# Devices.net
KiCad netlist of a schematic drawn in Altium Designer
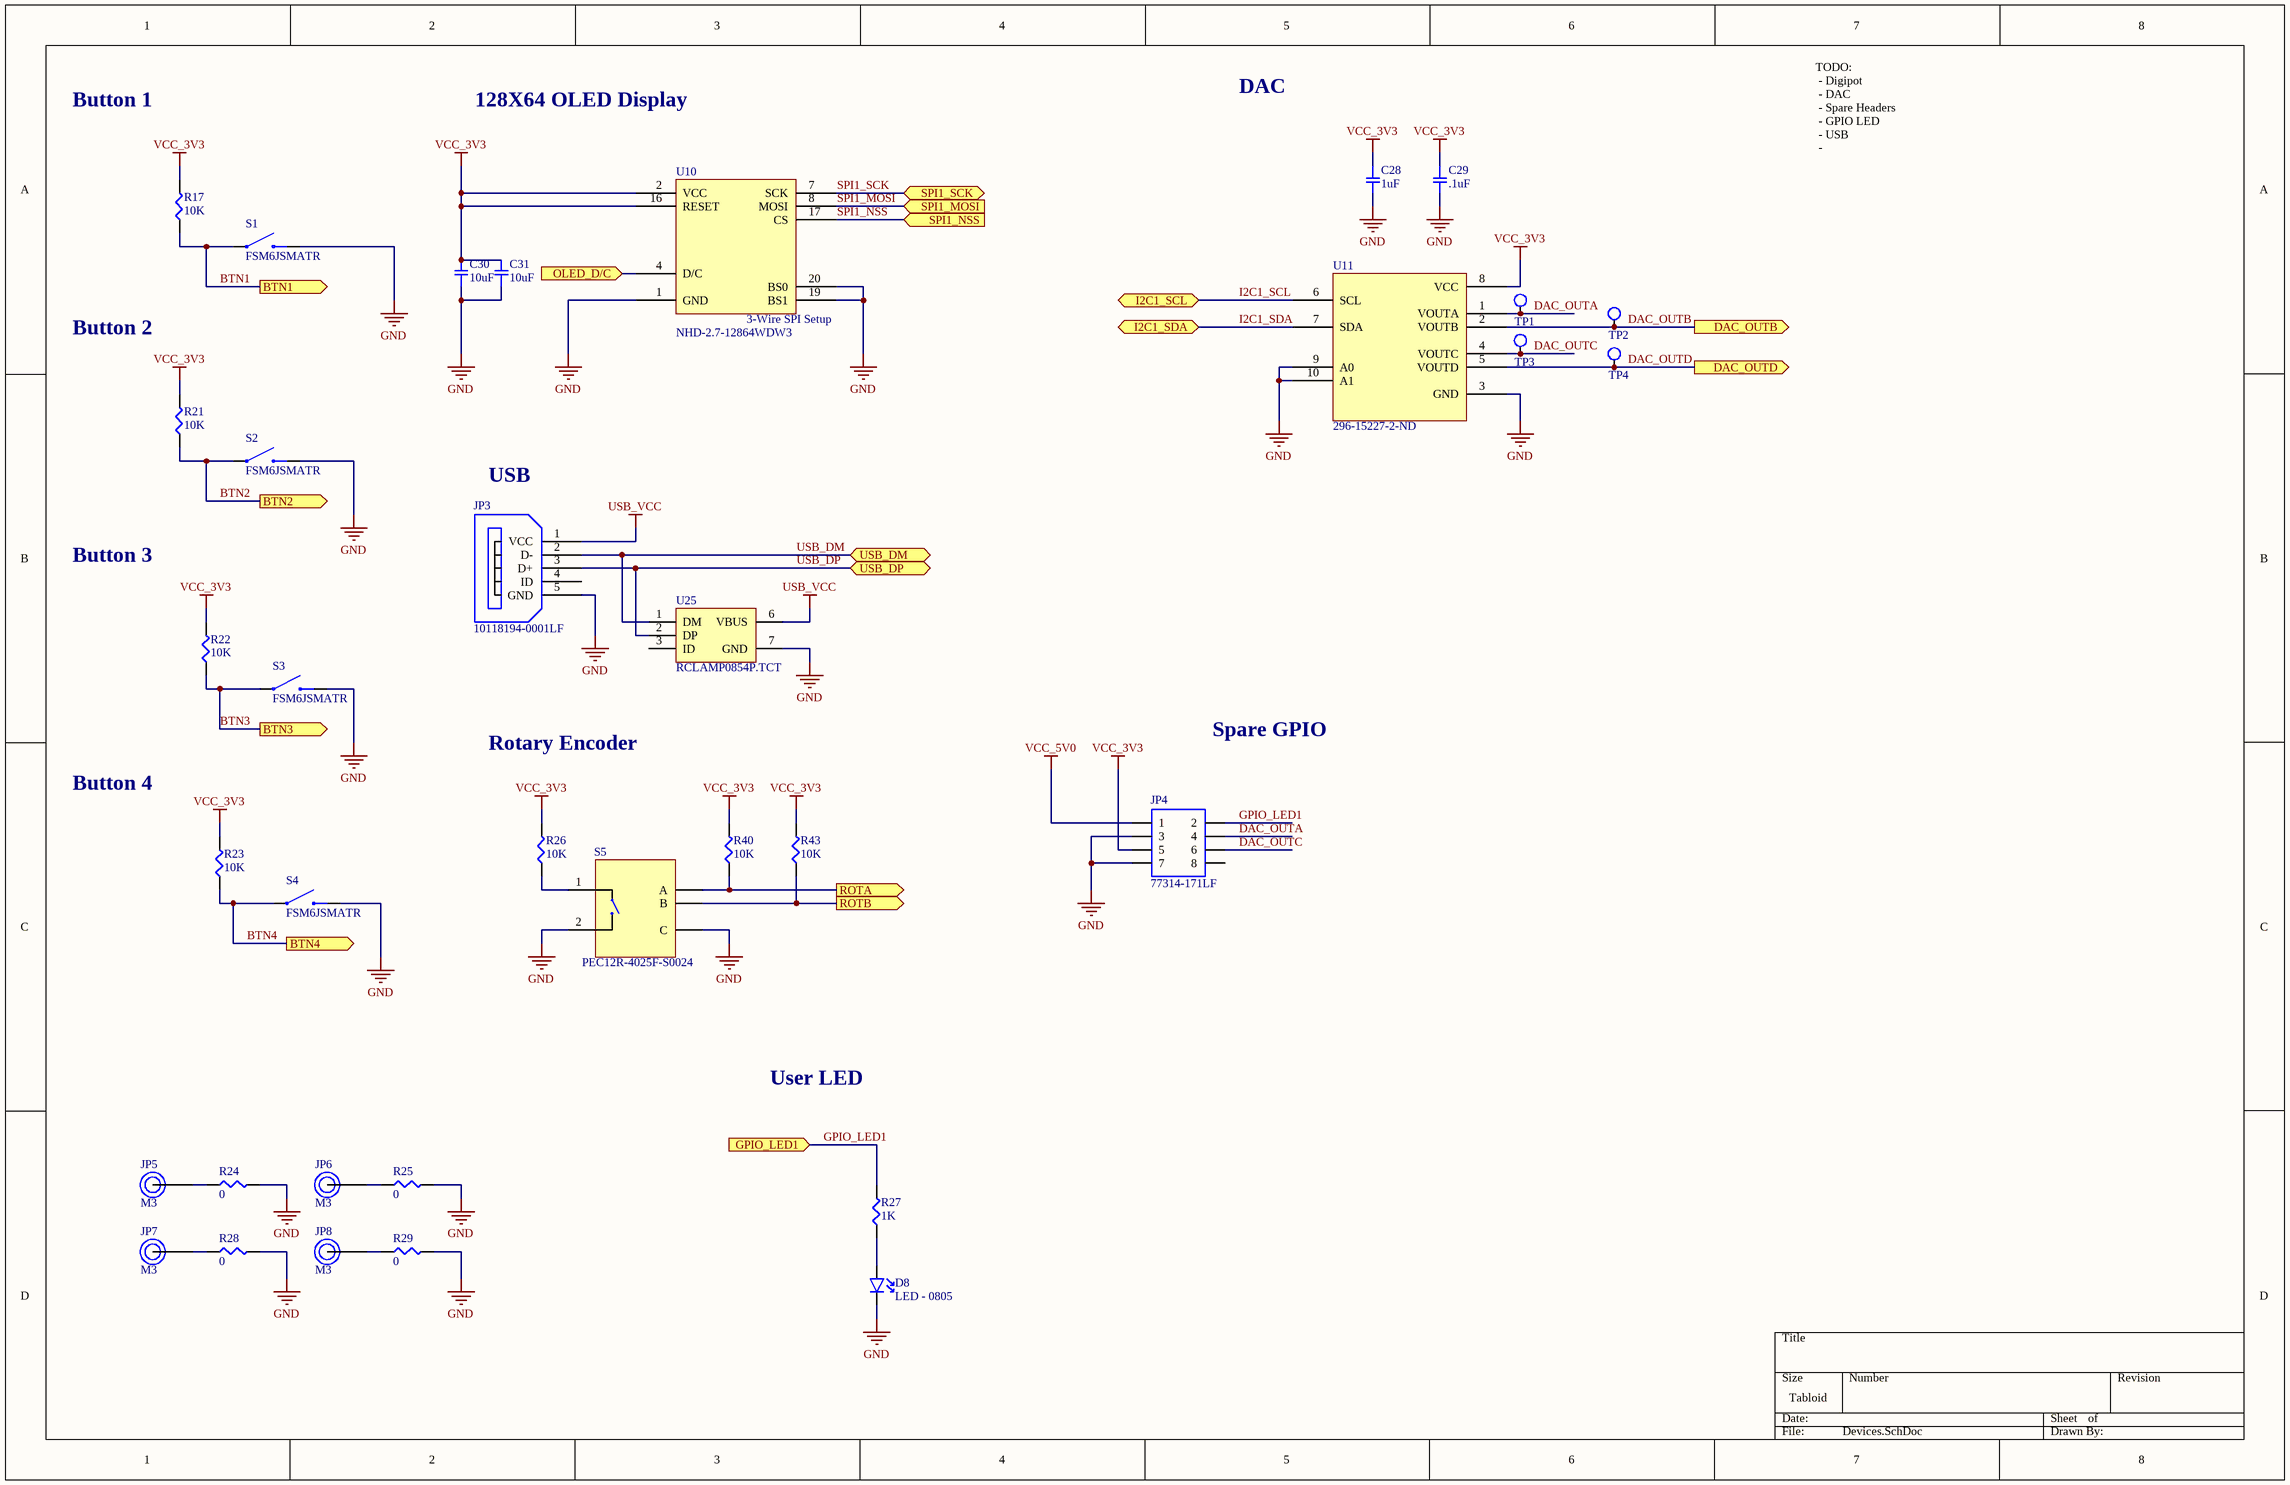
[diagram p0: Devices.SchDoc]

(export (version "E")
  (design (tool "Eeschema 10.0.6"))
  (components
    (comp (ref "C28")
      (value "1uF")
      (footprint "SMD-0603C")
      (description "CAP CER 0.022UF 50V X7R 0603")
      (fields
        (field (name "DIGI-KEY PART NUMBER") "490-5851-1-ND")
        (field (name "PART NUMBER") "GCJ188R71H223KA01D")
      )
      (libsource (lib "capacitor_murata_0603") (part "GCJ188R71H223KA01D"))
    )
    (comp (ref "C29")
      (value ".1uF")
      (footprint "SMD-0603C")
      (description "CAP CER 0.022UF 50V X7R 0603")
      (fields
        (field (name "DIGI-KEY PART NUMBER") "490-5851-1-ND")
        (field (name "PART NUMBER") "GCJ188R71H223KA01D")
      )
      (libsource (lib "capacitor_murata_0603") (part "GCJ188R71H223KA01D"))
    )
    (comp (ref "C30")
      (value "10uF")
      (footprint "SMD-0805C")
      (description "CAP CER 0.1UF 16V X7R 0805")
      (fields
        (field (name "DIGI-KEY PART NUMBER") "490-4414-1-ND")
        (field (name "PART NUMBER") "LLA219R71C104MA01L")
      )
      (libsource (lib "capacitor_murata_0805") (part "LLA219R71C104MA01L"))
    )
    (comp (ref "C31")
      (value "10uF")
      (footprint "SMD-0805C")
      (description "CAP CER 0.1UF 16V X7R 0805")
      (fields
        (field (name "DIGI-KEY PART NUMBER") "490-4414-1-ND")
        (field (name "PART NUMBER") "LLA219R71C104MA01L")
      )
      (libsource (lib "capacitor_murata_0805") (part "LLA219R71C104MA01L"))
    )
    (comp (ref "D8")
      (value "LED - 0805")
      (footprint "0805 SMD")
      (libsource (lib "Personal_Library") (part "LED - 0805"))
    )
    (comp (ref "JP3")
      (value "10118194-0001LF")
      (footprint "014-439")
      (description "CONN RCPT USB2.0 MICRO B SMD R/A")
      (libsource (lib "Personal_Library") (part "CONN USB"))
    )
    (comp (ref "JP4")
      (value "77314-171LF")
      (footprint "2x4 Pin Header")
      (description "CONN HEADER VERT 8POS 2.54MM")
      (libsource (lib "Personal_Library") (part "CONN HEADER VERT 2x4"))
    )
    (comp (ref "JP5")
      (value "M3")
      (footprint "M3-Hole")
      (description "M3 MOUNT HOLE SIZE")
      (libsource (lib "Personal_Library") (part "HOLE MOUNT M3"))
    )
    (comp (ref "JP6")
      (value "M3")
      (footprint "M3-Hole")
      (description "M3 MOUNT HOLE SIZE")
      (libsource (lib "Personal_Library") (part "HOLE MOUNT M3"))
    )
    (comp (ref "JP7")
      (value "M3")
      (footprint "M3-Hole")
      (description "M3 MOUNT HOLE SIZE")
      (libsource (lib "Personal_Library") (part "HOLE MOUNT M3"))
    )
    (comp (ref "JP8")
      (value "M3")
      (footprint "M3-Hole")
      (description "M3 MOUNT HOLE SIZE")
      (libsource (lib "Personal_Library") (part "HOLE MOUNT M3"))
    )
    (comp (ref "R17")
      (value "10K")
      (footprint "SMD-0805-RES")
      (description "RES SMD 0.1 OHM 1% 1/2W 0805")
      (fields
        (field (name "PART NUMBER") "ERJ-6BWFR100V")
        (field (name "DIGI-KEY PART NUMBER") "P17589CT-ND")
      )
      (libsource (lib "Panasonic_ERJ_0805") (part "ERJ-6BWFR100V"))
    )
    (comp (ref "R21")
      (value "10K")
      (footprint "SMD-0805-RES")
      (description "RES SMD 0.1 OHM 1% 1/2W 0805")
      (fields
        (field (name "PART NUMBER") "ERJ-6BWFR100V")
        (field (name "DIGI-KEY PART NUMBER") "P17589CT-ND")
      )
      (libsource (lib "Panasonic_ERJ_0805") (part "ERJ-6BWFR100V"))
    )
    (comp (ref "R22")
      (value "10K")
      (footprint "SMD-0805-RES")
      (description "RES SMD 0.1 OHM 1% 1/2W 0805")
      (fields
        (field (name "PART NUMBER") "ERJ-6BWFR100V")
        (field (name "DIGI-KEY PART NUMBER") "P17589CT-ND")
      )
      (libsource (lib "Panasonic_ERJ_0805") (part "ERJ-6BWFR100V"))
    )
    (comp (ref "R23")
      (value "10K")
      (footprint "SMD-0805-RES")
      (description "RES SMD 0.1 OHM 1% 1/2W 0805")
      (fields
        (field (name "PART NUMBER") "ERJ-6BWFR100V")
        (field (name "DIGI-KEY PART NUMBER") "P17589CT-ND")
      )
      (libsource (lib "Panasonic_ERJ_0805") (part "ERJ-6BWFR100V"))
    )
    (comp (ref "R24")
      (value "0")
      (footprint "SMD-0603-RES")
      (description "RES SMD 0.33 OHM 1% 1/4W 0603")
      (fields (field (name "PART NUMBER") "ERJ-3BQFR33V") (field (name "DIGI-KEY PART NUMBER") "P17396CT-ND"))
      (libsource (lib "Panasonic_ERJ_0603") (part "ERJ-3BQFR33V"))
    )
    (comp (ref "R25")
      (value "0")
      (footprint "SMD-0603-RES")
      (description "RES SMD 0.33 OHM 1% 1/4W 0603")
      (fields (field (name "PART NUMBER") "ERJ-3BQFR33V") (field (name "DIGI-KEY PART NUMBER") "P17396CT-ND"))
      (libsource (lib "Panasonic_ERJ_0603") (part "ERJ-3BQFR33V"))
    )
    (comp (ref "R26")
      (value "10K")
      (footprint "SMD-0805-RES")
      (description "RES SMD 0.1 OHM 1% 1/2W 0805")
      (fields
        (field (name "PART NUMBER") "ERJ-6BWFR100V")
        (field (name "DIGI-KEY PART NUMBER") "P17589CT-ND")
      )
      (libsource (lib "Panasonic_ERJ_0805") (part "ERJ-6BWFR100V"))
    )
    (comp (ref "R27")
      (value "1K")
      (footprint "SMD-0603-RES")
      (description "RES SMD 1.5 OHM 1% 1/4W 0603")
      (fields (field (name "PART NUMBER") "ERJ-3BQF1R5V") (field (name "DIGI-KEY PART NUMBER") "P15988CT-ND"))
      (libsource (lib "Panasonic_ERJ_0603") (part "ERJ-3BQF1R5V"))
    )
    (comp (ref "R28")
      (value "0")
      (footprint "SMD-0603-RES")
      (description "RES SMD 0.33 OHM 1% 1/4W 0603")
      (fields (field (name "PART NUMBER") "ERJ-3BQFR33V") (field (name "DIGI-KEY PART NUMBER") "P17396CT-ND"))
      (libsource (lib "Panasonic_ERJ_0603") (part "ERJ-3BQFR33V"))
    )
    (comp (ref "R29")
      (value "0")
      (footprint "SMD-0603-RES")
      (description "RES SMD 0.33 OHM 1% 1/4W 0603")
      (fields (field (name "PART NUMBER") "ERJ-3BQFR33V") (field (name "DIGI-KEY PART NUMBER") "P17396CT-ND"))
      (libsource (lib "Panasonic_ERJ_0603") (part "ERJ-3BQFR33V"))
    )
    (comp (ref "R40")
      (value "10K")
      (footprint "SMD-0805-RES")
      (description "RES SMD 0.1 OHM 1% 1/2W 0805")
      (fields
        (field (name "PART NUMBER") "ERJ-6BWFR100V")
        (field (name "DIGI-KEY PART NUMBER") "P17589CT-ND")
      )
      (libsource (lib "Panasonic_ERJ_0805") (part "ERJ-6BWFR100V"))
    )
    (comp (ref "R43")
      (value "10K")
      (footprint "SMD-0805-RES")
      (description "RES SMD 0.1 OHM 1% 1/2W 0805")
      (fields
        (field (name "PART NUMBER") "ERJ-6BWFR100V")
        (field (name "DIGI-KEY PART NUMBER") "P17589CT-ND")
      )
      (libsource (lib "Panasonic_ERJ_0805") (part "ERJ-6BWFR100V"))
    )
    (comp (ref "S1")
      (value "FSM6JSMATR")
      (footprint "TACTILE 4 PIN SMD 6MM")
      (description "SWITCH TACTILE SPST-NO 0.05A 24V")
      (libsource (lib "Personal_Library") (part "SWITCH TACTILE SPST"))
    )
    (comp (ref "S2")
      (value "FSM6JSMATR")
      (footprint "TACTILE 4 PIN SMD 6MM")
      (description "SWITCH TACTILE SPST-NO 0.05A 24V")
      (libsource (lib "Personal_Library") (part "SWITCH TACTILE SPST"))
    )
    (comp (ref "S3")
      (value "FSM6JSMATR")
      (footprint "TACTILE 4 PIN SMD 6MM")
      (description "SWITCH TACTILE SPST-NO 0.05A 24V")
      (libsource (lib "Personal_Library") (part "SWITCH TACTILE SPST"))
    )
    (comp (ref "S4")
      (value "FSM6JSMATR")
      (footprint "TACTILE 4 PIN SMD 6MM")
      (description "SWITCH TACTILE SPST-NO 0.05A 24V")
      (libsource (lib "Personal_Library") (part "SWITCH TACTILE SPST"))
    )
    (comp (ref "S5")
      (value "PEC12R-4025F-S0024")
      (footprint "PEC12R-4025F-S")
      (description "Rotary Encoder Mechanical 24 Quadrature (Incremental) Vertical")
      (libsource (lib "Personal_Library") (part "RTRY ENCDR MECH 24PPR"))
    )
    (comp (ref "TP1")
      (value "TEST POINT 1MM")
      (footprint "TEST POINT")
      (description "1mm pad for test points")
      (libsource (lib "Personal_Library") (part "TEST POINT 1MM"))
    )
    (comp (ref "TP2")
      (value "TEST POINT 1MM")
      (footprint "TEST POINT")
      (description "1mm pad for test points")
      (libsource (lib "Personal_Library") (part "TEST POINT 1MM"))
    )
    (comp (ref "TP3")
      (value "TEST POINT 1MM")
      (footprint "TEST POINT")
      (description "1mm pad for test points")
      (libsource (lib "Personal_Library") (part "TEST POINT 1MM"))
    )
    (comp (ref "TP4")
      (value "TEST POINT 1MM")
      (footprint "TEST POINT")
      (description "1mm pad for test points")
      (libsource (lib "Personal_Library") (part "TEST POINT 1MM"))
    )
    (comp (ref "U10")
      (value "NHD-2.7-12864WDW3")
      (footprint "NHD-2.7-12864WDW3")
      (description "Graphic LCD Display Module  White OLED - Passive Matrix Parallel/Serial 2.7\" (68.58mm) 128 x 64")
      (libsource (lib "IC") (part "DISP OLED GRAPHIC 128X64 WHT"))
    )
    (comp (ref "U11")
      (value "296-15227-2-ND")
      (footprint "10-VSSOP")
      (description "IC DAC 12BIT V-OUT 10VSSOP")
      (libsource (lib "UniversalConverter_Parts") (part "IC DAC DAC7574IDGSR"))
    )
    (comp (ref "U25")
      (value "RCLAMP0854P.TCT")
      (footprint "6-UFDFN")
      (description "TVS DIODE 5.5VWM 30VC SLP1616P6")
      (libsource (lib "UniversalConverter_Parts") (part "IC RCLAMP0854P.TCT"))
    )
  )
  (nets
    (net (code "1") (name "/BTN1") (class "Default")
      (node (ref "R17") (pin "1") (pinfunction "1_1") (pintype "passive"))
      (node (ref "S1") (pin "1") (pinfunction "1_1") (pintype "passive"))
    )
    (net (code "2") (name "/BTN2") (class "Default")
      (node (ref "R21") (pin "1") (pinfunction "1_1") (pintype "passive"))
      (node (ref "S2") (pin "1") (pinfunction "1_1") (pintype "passive"))
    )
    (net (code "3") (name "/BTN3") (class "Default")
      (node (ref "R22") (pin "1") (pinfunction "1_1") (pintype "passive"))
      (node (ref "S3") (pin "1") (pinfunction "1_1") (pintype "passive"))
    )
    (net (code "4") (name "/BTN4") (class "Default")
      (node (ref "R23") (pin "1") (pinfunction "1_1") (pintype "passive"))
      (node (ref "S4") (pin "1") (pinfunction "1_1") (pintype "passive"))
    )
    (net (code "5") (name "/DAC_OUTA") (class "Default")
      (node (ref "JP4") (pin "4") (pinfunction "4_4") (pintype "passive"))
      (node (ref "TP1") (pin "1") (pinfunction "1_1") (pintype "passive"))
      (node (ref "U11") (pin "1") (pinfunction "VOUTA_1") (pintype "passive"))
    )
    (net (code "6") (name "/DAC_OUTB") (class "Default")
      (node (ref "TP2") (pin "1") (pinfunction "1_1") (pintype "passive"))
      (node (ref "U11") (pin "2") (pinfunction "VOUTB_2") (pintype "passive"))
    )
    (net (code "7") (name "/DAC_OUTC") (class "Default")
      (node (ref "JP4") (pin "6") (pinfunction "6_6") (pintype "passive"))
      (node (ref "TP3") (pin "1") (pinfunction "1_1") (pintype "passive"))
      (node (ref "U11") (pin "4") (pinfunction "VOUTC_4") (pintype "passive"))
    )
    (net (code "8") (name "/DAC_OUTD") (class "Default")
      (node (ref "TP4") (pin "1") (pinfunction "1_1") (pintype "passive"))
      (node (ref "U11") (pin "5") (pinfunction "VOUTD_5") (pintype "passive"))
    )
    (net (code "9") (name "/GPIO_LED1") (class "Default")
      (node (ref "JP4") (pin "2") (pinfunction "2_2") (pintype "passive"))
      (node (ref "R27") (pin "2") (pinfunction "2_2") (pintype "passive"))
    )
    (net (code "10") (name "/I2C1_SCL") (class "Default")
      (node (ref "U11") (pin "6") (pinfunction "SCL_6") (pintype "passive"))
    )
    (net (code "11") (name "/I2C1_SDA") (class "Default")
      (node (ref "U11") (pin "7") (pinfunction "SDA_7") (pintype "passive"))
    )
    (net (code "12") (name "/OLED_D{slash}C") (class "Default")
      (node (ref "U10") (pin "4") (pinfunction "D/C_4") (pintype "passive"))
    )
    (net (code "13") (name "/ROTA") (class "Default")
      (node (ref "R40") (pin "1") (pinfunction "1_1") (pintype "passive"))
      (node (ref "S5") (pin "A") (pinfunction "A_A") (pintype "passive"))
    )
    (net (code "14") (name "/ROTB") (class "Default")
      (node (ref "R43") (pin "1") (pinfunction "1_1") (pintype "passive"))
      (node (ref "S5") (pin "B") (pinfunction "B_B") (pintype "passive"))
    )
    (net (code "15") (name "/SPI1_MOSI") (class "Default")
      (node (ref "U10") (pin "8") (pinfunction "MOSI_8") (pintype "passive"))
    )
    (net (code "16") (name "/SPI1_NSS") (class "Default")
      (node (ref "U10") (pin "17") (pinfunction "CS_17") (pintype "passive"))
    )
    (net (code "17") (name "/SPI1_SCK") (class "Default")
      (node (ref "U10") (pin "7") (pinfunction "SCK_7") (pintype "passive"))
    )
    (net (code "18") (name "/USB_DM") (class "Default")
      (node (ref "JP3") (pin "2") (pinfunction "D-_2") (pintype "passive"))
      (node (ref "U25") (pin "1") (pinfunction "DM_1") (pintype "passive"))
    )
    (net (code "19") (name "/USB_DP") (class "Default")
      (node (ref "JP3") (pin "3") (pinfunction "D+_3") (pintype "passive"))
      (node (ref "U25") (pin "2") (pinfunction "DP_2") (pintype "passive"))
    )
    (net (code "20") (name "GND") (class "Default")
      (node (ref "C28") (pin "2") (pinfunction "2_2") (pintype "passive"))
      (node (ref "C29") (pin "2") (pinfunction "2_2") (pintype "passive"))
      (node (ref "C30") (pin "1") (pinfunction "1_1") (pintype "passive"))
      (node (ref "C31") (pin "1") (pinfunction "1_1") (pintype "passive"))
      (node (ref "D8") (pin "2") (pinfunction "2_2") (pintype "passive"))
      (node (ref "JP3") (pin "5") (pinfunction "GND_5") (pintype "passive"))
      (node (ref "JP4") (pin "3") (pinfunction "3_3") (pintype "passive"))
      (node (ref "JP4") (pin "7") (pinfunction "7_7") (pintype "passive"))
      (node (ref "R24") (pin "2") (pinfunction "2_2") (pintype "passive"))
      (node (ref "R25") (pin "2") (pinfunction "2_2") (pintype "passive"))
      (node (ref "R28") (pin "2") (pinfunction "2_2") (pintype "passive"))
      (node (ref "R29") (pin "2") (pinfunction "2_2") (pintype "passive"))
      (node (ref "S1") (pin "2") (pinfunction "2_2") (pintype "passive"))
      (node (ref "S2") (pin "2") (pinfunction "2_2") (pintype "passive"))
      (node (ref "S3") (pin "2") (pinfunction "2_2") (pintype "passive"))
      (node (ref "S4") (pin "2") (pinfunction "2_2") (pintype "passive"))
      (node (ref "S5") (pin "2") (pintype "passive"))
      (node (ref "S5") (pin "C") (pinfunction "C_C") (pintype "passive"))
      (node (ref "U10") (pin "1") (pinfunction "GND_1") (pintype "passive"))
      (node (ref "U10") (pin "19") (pinfunction "BS1_19") (pintype "passive"))
      (node (ref "U10") (pin "20") (pinfunction "BS0_20") (pintype "passive"))
      (node (ref "U11") (pin "10") (pinfunction "A1_10") (pintype "passive"))
      (node (ref "U11") (pin "3") (pinfunction "GND_3") (pintype "passive"))
      (node (ref "U11") (pin "9") (pinfunction "A0_9") (pintype "passive"))
      (node (ref "U25") (pin "7") (pinfunction "GND_7") (pintype "passive"))
    )
    (net (code "21") (name "Net-(D8-Pad1)") (class "Default")
      (node (ref "D8") (pin "1") (pinfunction "1_1") (pintype "passive"))
      (node (ref "R27") (pin "1") (pinfunction "1_1") (pintype "passive"))
    )
    (net (code "22") (name "Net-(JP5-Pad1)") (class "Default")
      (node (ref "JP5") (pin "1") (pinfunction "1_1") (pintype "passive"))
      (node (ref "R24") (pin "1") (pinfunction "1_1") (pintype "passive"))
    )
    (net (code "23") (name "Net-(JP6-Pad1)") (class "Default")
      (node (ref "JP6") (pin "1") (pinfunction "1_1") (pintype "passive"))
      (node (ref "R25") (pin "1") (pinfunction "1_1") (pintype "passive"))
    )
    (net (code "24") (name "Net-(JP7-Pad1)") (class "Default")
      (node (ref "JP7") (pin "1") (pinfunction "1_1") (pintype "passive"))
      (node (ref "R28") (pin "1") (pinfunction "1_1") (pintype "passive"))
    )
    (net (code "25") (name "Net-(JP8-Pad1)") (class "Default")
      (node (ref "JP8") (pin "1") (pinfunction "1_1") (pintype "passive"))
      (node (ref "R29") (pin "1") (pinfunction "1_1") (pintype "passive"))
    )
    (net (code "26") (name "Net-(R26-Pad1)") (class "Default")
      (node (ref "R26") (pin "1") (pinfunction "1_1") (pintype "passive"))
      (node (ref "S5") (pin "1") (pinfunction "1_1") (pintype "passive"))
    )
    (net (code "27") (name "USB_VCC") (class "Default")
      (node (ref "JP3") (pin "1") (pinfunction "VCC_1") (pintype "passive"))
      (node (ref "U25") (pin "6") (pinfunction "VBUS_6") (pintype "passive"))
    )
    (net (code "28") (name "VCC_3V3") (class "Default")
      (node (ref "C28") (pin "1") (pinfunction "1_1") (pintype "passive"))
      (node (ref "C29") (pin "1") (pinfunction "1_1") (pintype "passive"))
      (node (ref "C30") (pin "2") (pinfunction "2_2") (pintype "passive"))
      (node (ref "C31") (pin "2") (pinfunction "2_2") (pintype "passive"))
      (node (ref "JP4") (pin "5") (pinfunction "5_5") (pintype "passive"))
      (node (ref "R17") (pin "2") (pinfunction "2_2") (pintype "passive"))
      (node (ref "R21") (pin "2") (pinfunction "2_2") (pintype "passive"))
      (node (ref "R22") (pin "2") (pinfunction "2_2") (pintype "passive"))
      (node (ref "R23") (pin "2") (pinfunction "2_2") (pintype "passive"))
      (node (ref "R26") (pin "2") (pinfunction "2_2") (pintype "passive"))
      (node (ref "R40") (pin "2") (pinfunction "2_2") (pintype "passive"))
      (node (ref "R43") (pin "2") (pinfunction "2_2") (pintype "passive"))
      (node (ref "U10") (pin "16") (pinfunction "RESET_16") (pintype "passive"))
      (node (ref "U10") (pin "2") (pinfunction "VCC_2") (pintype "passive"))
      (node (ref "U11") (pin "8") (pinfunction "VCC_8") (pintype "passive"))
    )
    (net (code "29") (name "VCC_5V0") (class "Default")
      (node (ref "JP4") (pin "1") (pinfunction "1_1") (pintype "passive"))
    )
    (net (code "30") (name "unconnected-(JP3-ID-Pad4)") (class "Default")
      (node (ref "JP3") (pin "4") (pinfunction "ID_4") (pintype "passive"))
    )
    (net (code "31") (name "unconnected-(JP4-Pad8)") (class "Default")
      (node (ref "JP4") (pin "8") (pinfunction "8_8") (pintype "passive"))
    )
    (net (code "32") (name "unconnected-(U25-ID-Pad3)") (class "Default")
      (node (ref "U25") (pin "3") (pinfunction "ID_3") (pintype "passive"))
    )
  )
)
